# ard_220v_vent.net
KiCad netlist of a schematic drawn in EAGLE
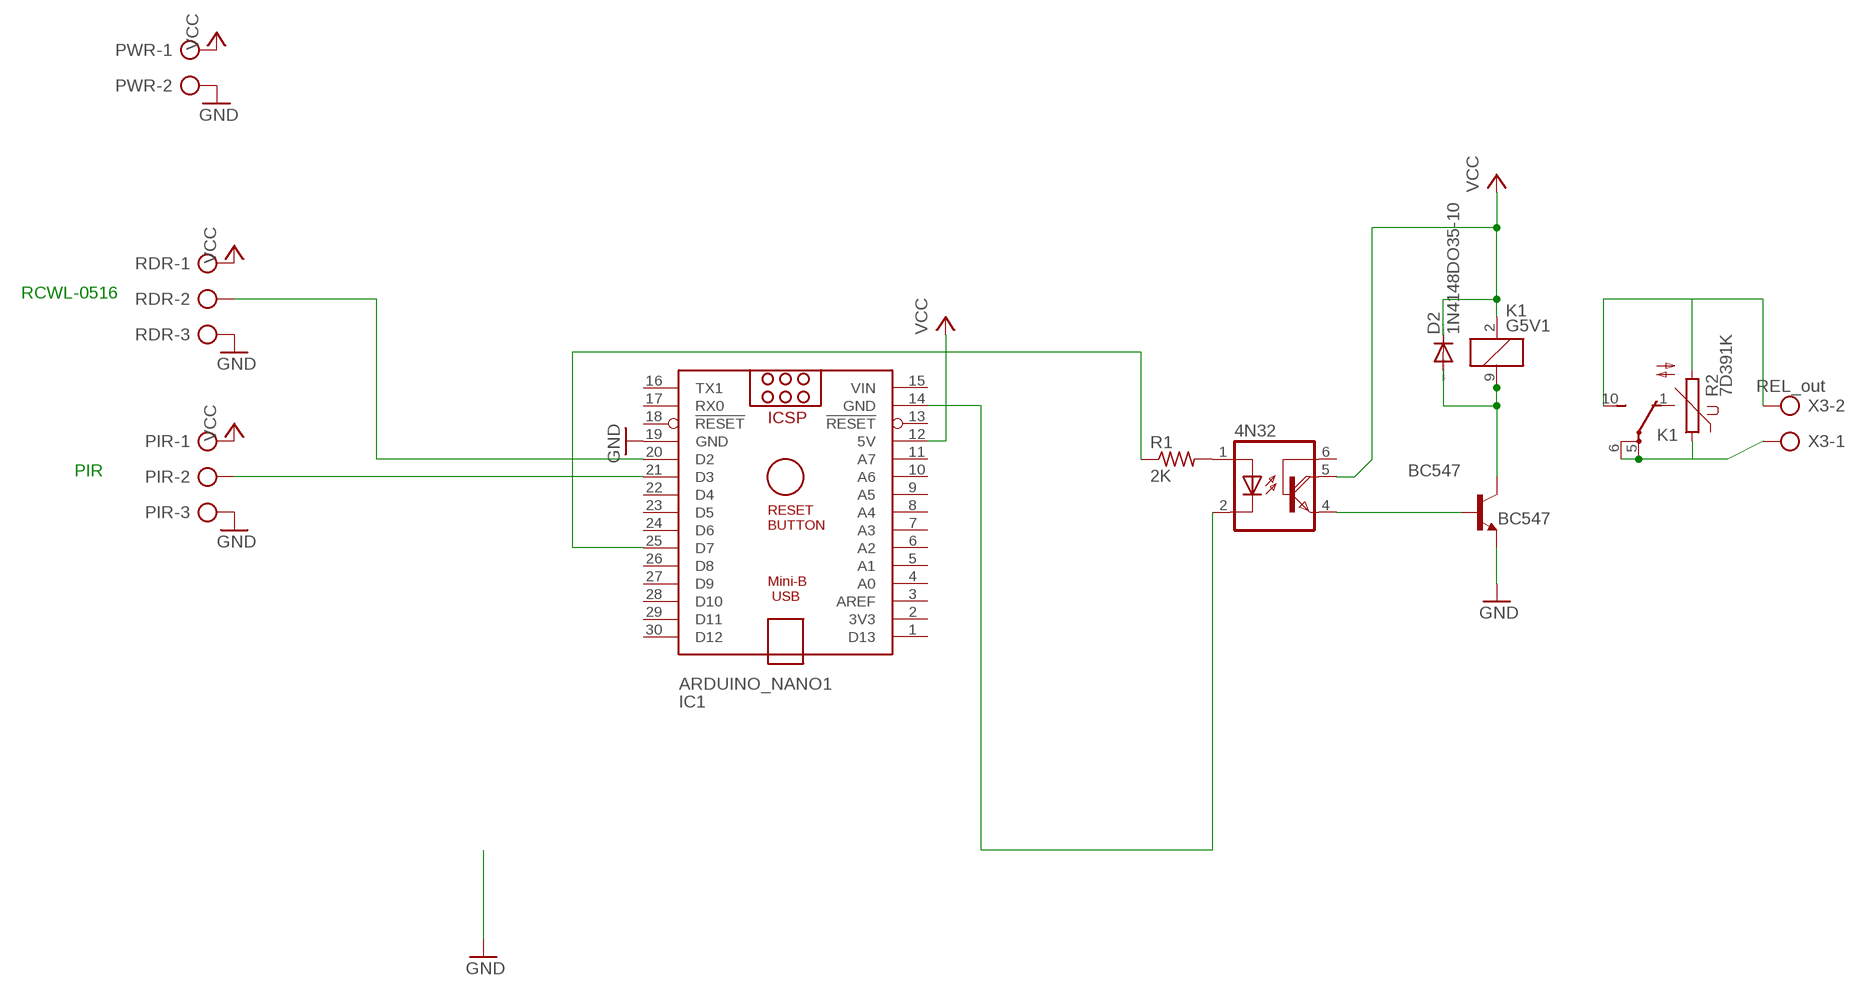
[diagram p0: schematic, sheet 1]

(export (version "E")
  (design (tool "Eeschema 10.0.6"))
  (components
    (comp (ref "4N32")
      (value "4N33")
      (footprint "eagle-import:DIL06")
      (fields (field (name "MF") "VISHAY/TELEFUNKEN") (field (name "MPN") "4N32"))
      (libsource (lib "eagle-import") (part "4N33"))
    )
    (comp (ref "ARDUINO_NANO1")
      (value "IC1")
      (footprint "eagle-import:ARDUINO_NANO")
      (libsource (lib "eagle-import") (part "ARDUINO_NANO"))
    )
    (comp (ref "BC547")
      (value "BC547")
      (footprint "eagle-import:TO92")
      (libsource (lib "eagle-import") (part "BC547"))
    )
    (comp (ref "D2")
      (value "1N4148DO35-10")
      (footprint "eagle-import:DO35-10")
      (libsource (lib "eagle-import") (part "1N4148DO35-10"))
    )
    (comp (ref "K1")
      (value "G5V1")
      (footprint "eagle-import:G5V1")
      (fields (field (name "MPN") "G5V-1-DC24"))
      (libsource (lib "eagle-import") (part "G5V1"))
    )
    (comp (ref "PIR")
      (value "AK500/3")
      (footprint "eagle-import:AK500_3")
      (libsource (lib "eagle-import") (part "AK500/3"))
    )
    (comp (ref "PWR")
      (value "AK500/2")
      (footprint "eagle-import:AK500_2")
      (libsource (lib "eagle-import") (part "AK500/2"))
    )
    (comp (ref "R1")
      (value "2K")
      (footprint "eagle-import:0207_10")
      (libsource (lib "eagle-import") (part "R-US_0207/10"))
    )
    (comp (ref "R2")
      (value "7D391K")
      (footprint "eagle-import:S07K385")
      (libsource (lib "eagle-import") (part "S07K385"))
    )
    (comp (ref "RDR")
      (value "AK500/3")
      (footprint "eagle-import:AK500_3")
      (libsource (lib "eagle-import") (part "AK500/3"))
    )
    (comp (ref "X3")
      (value "REL_out")
      (footprint "eagle-import:AK500_2")
      (libsource (lib "eagle-import") (part "AK500/2"))
    )
  )
  (nets
    (net (code "1") (name "/VIN") (class "Default")
      (node (ref "ARDUINO_NANO1") (pin "15") (pinfunction "VIN_15") (pintype "power_in"))
    )
    (net (code "2") (name "GND") (class "Default")
      (node (ref "ARDUINO_NANO1") (pin "19") (pinfunction "GND_19") (pintype "power_in"))
      (node (ref "BC547") (pin "1") (pinfunction "E_1") (pintype "passive"))
      (node (ref "PIR") (pin "3") (pinfunction "KL_3") (pintype "passive"))
      (node (ref "PWR") (pin "2") (pinfunction "KL_2") (pintype "passive"))
      (node (ref "RDR") (pin "3") (pinfunction "KL_3") (pintype "passive"))
    )
    (net (code "3") (name "Net-(4N32-A)") (class "Default")
      (node (ref "4N32") (pin "1") (pinfunction "A_1") (pintype "passive"))
      (node (ref "R1") (pin "2") (pinfunction "2_2") (pintype "passive"))
    )
    (net (code "4") (name "Net-(4N32-C)") (class "Default")
      (node (ref "4N32") (pin "2") (pinfunction "C_2") (pintype "passive"))
      (node (ref "ARDUINO_NANO1") (pin "14") (pinfunction "GND_14") (pintype "power_in"))
    )
    (net (code "5") (name "Net-(4N32-E)") (class "Default")
      (node (ref "4N32") (pin "4") (pinfunction "E_4") (pintype "passive"))
      (node (ref "BC547") (pin "2") (pinfunction "B_2") (pintype "passive"))
    )
    (net (code "6") (name "Net-(ARDUINO_NANO1-D2)") (class "Default")
      (node (ref "ARDUINO_NANO1") (pin "20") (pinfunction "D2_20") (pintype "bidirectional"))
      (node (ref "RDR") (pin "2") (pinfunction "KL_2") (pintype "passive"))
    )
    (net (code "7") (name "Net-(ARDUINO_NANO1-D3)") (class "Default")
      (node (ref "ARDUINO_NANO1") (pin "21") (pinfunction "D3_21") (pintype "bidirectional"))
      (node (ref "PIR") (pin "2") (pinfunction "KL_2") (pintype "passive"))
    )
    (net (code "8") (name "Net-(ARDUINO_NANO1-D7)") (class "Default")
      (node (ref "ARDUINO_NANO1") (pin "25") (pinfunction "D7_25") (pintype "bidirectional"))
      (node (ref "R1") (pin "1") (pinfunction "1_1") (pintype "passive"))
    )
    (net (code "9") (name "Net-(BC547-C)") (class "Default")
      (node (ref "BC547") (pin "3") (pinfunction "C_3") (pintype "passive"))
      (node (ref "D2") (pin "A") (pinfunction "A_A") (pintype "passive"))
      (node (ref "K1") (pin "9") (pinfunction "2_9") (pintype "passive"))
    )
    (net (code "10") (name "Net-(K1B-S)") (class "Default")
      (node (ref "K1") (pin "10") (pinfunction "S_10") (pintype "passive"))
      (node (ref "R2") (pin "2") (pinfunction "2_2") (pintype "passive"))
      (node (ref "X3") (pin "2") (pinfunction "KL_2") (pintype "passive"))
    )
    (net (code "11") (name "Net-(X3A-KL)") (class "Default")
      (node (ref "K1") (pin "5") (pinfunction "P_5") (pintype "passive"))
      (node (ref "K1") (pin "6") (pinfunction "P_6") (pintype "passive"))
      (node (ref "R2") (pin "1") (pinfunction "1_1") (pintype "passive"))
      (node (ref "X3") (pin "1") (pinfunction "KL_1") (pintype "passive"))
    )
    (net (code "12") (name "VCC") (class "Default")
      (node (ref "4N32") (pin "5") (pinfunction "COL_5") (pintype "passive"))
      (node (ref "ARDUINO_NANO1") (pin "12") (pinfunction "5V_12") (pintype "power_in"))
      (node (ref "D2") (pin "C") (pinfunction "C_C") (pintype "passive"))
      (node (ref "K1") (pin "2") (pinfunction "1_2") (pintype "passive"))
      (node (ref "PIR") (pin "1") (pinfunction "KL_1") (pintype "passive"))
      (node (ref "PWR") (pin "1") (pinfunction "KL_1") (pintype "passive"))
      (node (ref "RDR") (pin "1") (pinfunction "KL_1") (pintype "passive"))
    )
    (net (code "13") (name "unconnected-(4N32-B-Pad6)") (class "Default")
      (node (ref "4N32") (pin "6") (pinfunction "B_6") (pintype "passive"))
    )
    (net (code "14") (name "unconnected-(ARDUINO_NANO1-3V3-Pad2)") (class "Default")
      (node (ref "ARDUINO_NANO1") (pin "2") (pinfunction "3V3_2") (pintype "output"))
    )
    (net (code "15") (name "unconnected-(ARDUINO_NANO1-A0-Pad4)") (class "Default")
      (node (ref "ARDUINO_NANO1") (pin "4") (pinfunction "A0_4") (pintype "bidirectional"))
    )
    (net (code "16") (name "unconnected-(ARDUINO_NANO1-A1-Pad5)") (class "Default")
      (node (ref "ARDUINO_NANO1") (pin "5") (pinfunction "A1_5") (pintype "bidirectional"))
    )
    (net (code "17") (name "unconnected-(ARDUINO_NANO1-A2-Pad6)") (class "Default")
      (node (ref "ARDUINO_NANO1") (pin "6") (pinfunction "A2_6") (pintype "bidirectional"))
    )
    (net (code "18") (name "unconnected-(ARDUINO_NANO1-A3-Pad7)") (class "Default")
      (node (ref "ARDUINO_NANO1") (pin "7") (pinfunction "A3_7") (pintype "bidirectional"))
    )
    (net (code "19") (name "unconnected-(ARDUINO_NANO1-A4-Pad8)") (class "Default")
      (node (ref "ARDUINO_NANO1") (pin "8") (pinfunction "A4_8") (pintype "bidirectional"))
    )
    (net (code "20") (name "unconnected-(ARDUINO_NANO1-A5-Pad9)") (class "Default")
      (node (ref "ARDUINO_NANO1") (pin "9") (pinfunction "A5_9") (pintype "bidirectional"))
    )
    (net (code "21") (name "unconnected-(ARDUINO_NANO1-A6-Pad10)") (class "Default")
      (node (ref "ARDUINO_NANO1") (pin "10") (pinfunction "A6_10") (pintype "bidirectional"))
    )
    (net (code "22") (name "unconnected-(ARDUINO_NANO1-A7-Pad11)") (class "Default")
      (node (ref "ARDUINO_NANO1") (pin "11") (pinfunction "A7_11") (pintype "bidirectional"))
    )
    (net (code "23") (name "unconnected-(ARDUINO_NANO1-AREF-Pad3)") (class "Default")
      (node (ref "ARDUINO_NANO1") (pin "3") (pinfunction "AREF_3") (pintype "input"))
    )
    (net (code "24") (name "unconnected-(ARDUINO_NANO1-D4-Pad22)") (class "Default")
      (node (ref "ARDUINO_NANO1") (pin "22") (pinfunction "D4_22") (pintype "bidirectional"))
    )
    (net (code "25") (name "unconnected-(ARDUINO_NANO1-D5-Pad23)") (class "Default")
      (node (ref "ARDUINO_NANO1") (pin "23") (pinfunction "D5_23") (pintype "bidirectional"))
    )
    (net (code "26") (name "unconnected-(ARDUINO_NANO1-D6-Pad24)") (class "Default")
      (node (ref "ARDUINO_NANO1") (pin "24") (pinfunction "D6_24") (pintype "bidirectional"))
    )
    (net (code "27") (name "unconnected-(ARDUINO_NANO1-D8-Pad26)") (class "Default")
      (node (ref "ARDUINO_NANO1") (pin "26") (pinfunction "D8_26") (pintype "bidirectional"))
    )
    (net (code "28") (name "unconnected-(ARDUINO_NANO1-D9-Pad27)") (class "Default")
      (node (ref "ARDUINO_NANO1") (pin "27") (pinfunction "D9_27") (pintype "bidirectional"))
    )
    (net (code "29") (name "unconnected-(ARDUINO_NANO1-D10-Pad28)") (class "Default")
      (node (ref "ARDUINO_NANO1") (pin "28") (pinfunction "D10_28") (pintype "bidirectional"))
    )
    (net (code "30") (name "unconnected-(ARDUINO_NANO1-D11-Pad29)") (class "Default")
      (node (ref "ARDUINO_NANO1") (pin "29") (pinfunction "D11_29") (pintype "bidirectional"))
    )
    (net (code "31") (name "unconnected-(ARDUINO_NANO1-D12-Pad30)") (class "Default")
      (node (ref "ARDUINO_NANO1") (pin "30") (pinfunction "D12_30") (pintype "bidirectional"))
    )
    (net (code "32") (name "unconnected-(ARDUINO_NANO1-D13-Pad1)") (class "Default")
      (node (ref "ARDUINO_NANO1") (pin "1") (pinfunction "D13_1") (pintype "bidirectional"))
    )
    (net (code "33") (name "unconnected-(ARDUINO_NANO1-RX0-Pad17)") (class "Default")
      (node (ref "ARDUINO_NANO1") (pin "17") (pinfunction "RX0_17") (pintype "bidirectional"))
    )
    (net (code "34") (name "unconnected-(ARDUINO_NANO1-TX1-Pad16)") (class "Default")
      (node (ref "ARDUINO_NANO1") (pin "16") (pinfunction "TX1_16") (pintype "bidirectional"))
    )
    (net (code "35") (name "unconnected-(ARDUINO_NANO1-~{RESET}-Pad13)") (class "Default")
      (node (ref "ARDUINO_NANO1") (pin "13") (pinfunction "~{RESET}_13") (pintype "input"))
    )
    (net (code "36") (name "unconnected-(ARDUINO_NANO1-~{RESET}-Pad18)") (class "Default")
      (node (ref "ARDUINO_NANO1") (pin "18") (pinfunction "~{RESET}_18") (pintype "input"))
    )
    (net (code "37") (name "unconnected-(K1B-O-Pad1)") (class "Default")
      (node (ref "K1") (pin "1") (pinfunction "O_1") (pintype "passive"))
    )
  )
)
